# sentinel_psionic_driver.net
KiCad netlist of a schematic drawn in EAGLE
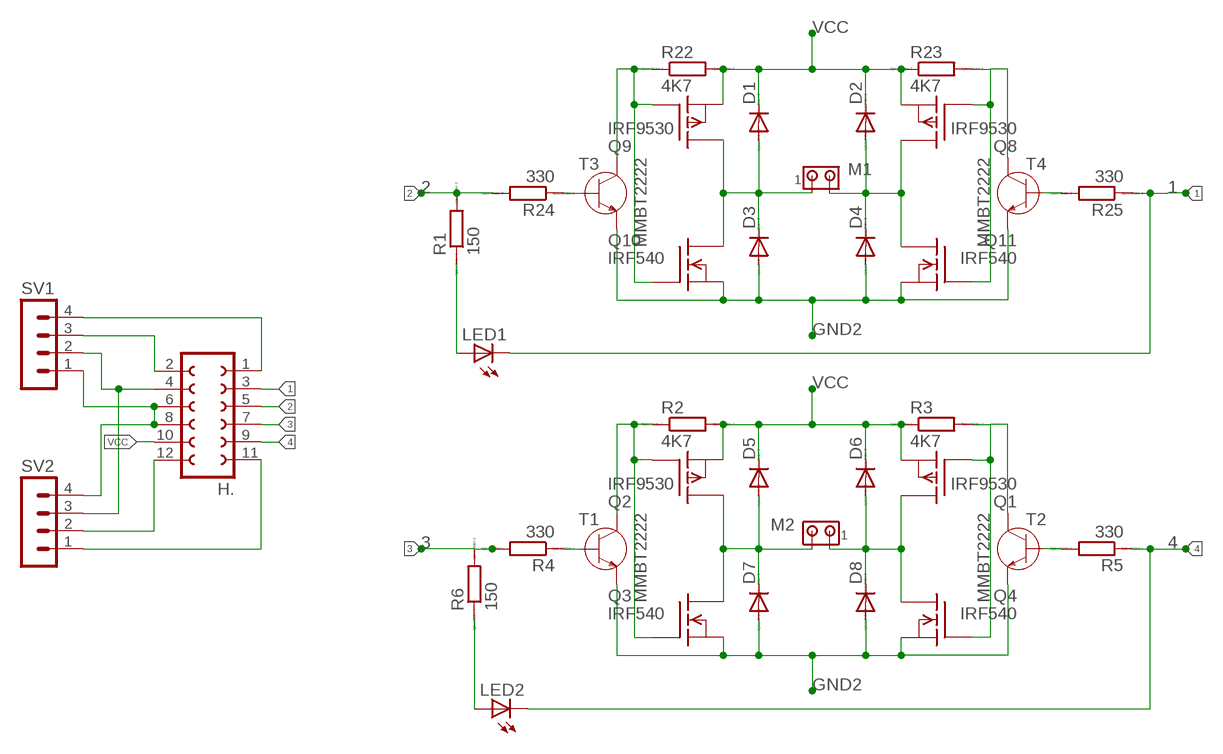
[diagram p0: schematic, sheet 1]

(export (version "E")
  (design (tool "Eeschema 10.0.6"))
  (components
    (comp (ref "D1")
      (value "DIODE-DO-214AC")
      (footprint "eagle-import:DO-214AC")
      (libsource (lib "eagle-import") (part "DIODE-DO-214AC"))
    )
    (comp (ref "D2")
      (value "DIODE-DO-214AC")
      (footprint "eagle-import:DO-214AC")
      (libsource (lib "eagle-import") (part "DIODE-DO-214AC"))
    )
    (comp (ref "D3")
      (value "DIODE-DO-214AC")
      (footprint "eagle-import:DO-214AC")
      (libsource (lib "eagle-import") (part "DIODE-DO-214AC"))
    )
    (comp (ref "D4")
      (value "DIODE-DO-214AC")
      (footprint "eagle-import:DO-214AC")
      (libsource (lib "eagle-import") (part "DIODE-DO-214AC"))
    )
    (comp (ref "D5")
      (value "DIODE-DO-214AC")
      (footprint "eagle-import:DO-214AC")
      (libsource (lib "eagle-import") (part "DIODE-DO-214AC"))
    )
    (comp (ref "D6")
      (value "DIODE-DO-214AC")
      (footprint "eagle-import:DO-214AC")
      (libsource (lib "eagle-import") (part "DIODE-DO-214AC"))
    )
    (comp (ref "D7")
      (value "DIODE-DO-214AC")
      (footprint "eagle-import:DO-214AC")
      (libsource (lib "eagle-import") (part "DIODE-DO-214AC"))
    )
    (comp (ref "D8")
      (value "DIODE-DO-214AC")
      (footprint "eagle-import:DO-214AC")
      (libsource (lib "eagle-import") (part "DIODE-DO-214AC"))
    )
    (comp (ref "H.")
      (value "FE06-2")
      (footprint "eagle-import:FE06-2")
      (libsource (lib "eagle-import") (part "FE06-2"))
    )
    (comp (ref "LED1")
      (value "LED3MM")
      (footprint "eagle-import:LED3MM")
      (libsource (lib "eagle-import") (part "LED3MM"))
    )
    (comp (ref "LED2")
      (value "LED3MM")
      (footprint "eagle-import:LED3MM")
      (libsource (lib "eagle-import") (part "LED3MM"))
    )
    (comp (ref "M1")
      (value "MTA02-100")
      (footprint "eagle-import:10X02MTA")
      (libsource (lib "eagle-import") (part "MTA02-100"))
    )
    (comp (ref "M2")
      (value "MTA02-100")
      (footprint "eagle-import:10X02MTA")
      (libsource (lib "eagle-import") (part "MTA02-100"))
    )
    (comp (ref "Q1")
      (value "IRF9530")
      (footprint "eagle-import:TO220")
      (libsource (lib "eagle-import") (part "IRF9530"))
    )
    (comp (ref "Q2")
      (value "IRF9530")
      (footprint "eagle-import:TO220")
      (libsource (lib "eagle-import") (part "IRF9530"))
    )
    (comp (ref "Q3")
      (value "IRF540")
      (footprint "eagle-import:TO220")
      (libsource (lib "eagle-import") (part "IRF540"))
    )
    (comp (ref "Q4")
      (value "IRF540")
      (footprint "eagle-import:TO220")
      (libsource (lib "eagle-import") (part "IRF540"))
    )
    (comp (ref "Q8")
      (value "IRF9530")
      (footprint "eagle-import:TO220")
      (libsource (lib "eagle-import") (part "IRF9530"))
    )
    (comp (ref "Q9")
      (value "IRF9530")
      (footprint "eagle-import:TO220")
      (libsource (lib "eagle-import") (part "IRF9530"))
    )
    (comp (ref "Q10")
      (value "IRF540")
      (footprint "eagle-import:TO220")
      (libsource (lib "eagle-import") (part "IRF540"))
    )
    (comp (ref "Q11")
      (value "IRF540")
      (footprint "eagle-import:TO220")
      (libsource (lib "eagle-import") (part "IRF540"))
    )
    (comp (ref "R1")
      (value "150")
      (footprint "eagle-import:R1206")
      (libsource (lib "eagle-import") (part "RR1206"))
    )
    (comp (ref "R2")
      (value "4K7")
      (footprint "eagle-import:R1206")
      (libsource (lib "eagle-import") (part "RR1206"))
    )
    (comp (ref "R3")
      (value "4K7")
      (footprint "eagle-import:R1206")
      (libsource (lib "eagle-import") (part "RR1206"))
    )
    (comp (ref "R4")
      (value "330")
      (footprint "eagle-import:R1206")
      (libsource (lib "eagle-import") (part "RR1206"))
    )
    (comp (ref "R5")
      (value "330")
      (footprint "eagle-import:R1206")
      (libsource (lib "eagle-import") (part "RR1206"))
    )
    (comp (ref "R6")
      (value "150")
      (footprint "eagle-import:R1206")
      (libsource (lib "eagle-import") (part "RR1206"))
    )
    (comp (ref "R22")
      (value "4K7")
      (footprint "eagle-import:R1206")
      (libsource (lib "eagle-import") (part "RR1206"))
    )
    (comp (ref "R23")
      (value "4K7")
      (footprint "eagle-import:R1206")
      (libsource (lib "eagle-import") (part "RR1206"))
    )
    (comp (ref "R24")
      (value "330")
      (footprint "eagle-import:R1206")
      (libsource (lib "eagle-import") (part "RR1206"))
    )
    (comp (ref "R25")
      (value "330")
      (footprint "eagle-import:R1206")
      (libsource (lib "eagle-import") (part "RR1206"))
    )
    (comp (ref "SV1")
      (value "MA04-1")
      (footprint "eagle-import:MA04-1")
      (libsource (lib "eagle-import") (part "MA04-1"))
    )
    (comp (ref "SV2")
      (value "MA04-1")
      (footprint "eagle-import:MA04-1")
      (libsource (lib "eagle-import") (part "MA04-1"))
    )
    (comp (ref "T1")
      (value "MMBT2222")
      (footprint "eagle-import:SOT23")
      (libsource (lib "eagle-import") (part "MMBT2222"))
    )
    (comp (ref "T2")
      (value "MMBT2222")
      (footprint "eagle-import:SOT23")
      (libsource (lib "eagle-import") (part "MMBT2222"))
    )
    (comp (ref "T3")
      (value "MMBT2222")
      (footprint "eagle-import:SOT23")
      (libsource (lib "eagle-import") (part "MMBT2222"))
    )
    (comp (ref "T4")
      (value "MMBT2222")
      (footprint "eagle-import:SOT23")
      (libsource (lib "eagle-import") (part "MMBT2222"))
    )
  )
  (nets
    (net (code "1") (name "/GND2") (class "Default")
      (node (ref "D3") (pin "A") (pinfunction "A_A") (pintype "passive"))
      (node (ref "D4") (pin "A") (pinfunction "A_A") (pintype "passive"))
      (node (ref "D7") (pin "A") (pinfunction "A_A") (pintype "passive"))
      (node (ref "D8") (pin "A") (pinfunction "A_A") (pintype "passive"))
      (node (ref "H.") (pin "6") (pinfunction "6_6") (pintype "passive"))
      (node (ref "H.") (pin "8") (pinfunction "8_8") (pintype "passive"))
      (node (ref "Q10") (pin "3") (pinfunction "S_3") (pintype "passive"))
      (node (ref "Q11") (pin "3") (pinfunction "S_3") (pintype "passive"))
      (node (ref "Q3") (pin "3") (pinfunction "S_3") (pintype "passive"))
      (node (ref "Q4") (pin "3") (pinfunction "S_3") (pintype "passive"))
      (node (ref "SV1") (pin "1") (pinfunction "1_1") (pintype "passive"))
      (node (ref "SV2") (pin "4") (pinfunction "4_4") (pintype "passive"))
      (node (ref "T1") (pin "2") (pinfunction "E_2") (pintype "passive"))
      (node (ref "T2") (pin "2") (pinfunction "E_2") (pintype "passive"))
      (node (ref "T3") (pin "2") (pinfunction "E_2") (pintype "passive"))
      (node (ref "T4") (pin "2") (pinfunction "E_2") (pintype "passive"))
    )
    (net (code "2") (name "1") (class "Default")
      (node (ref "H.") (pin "3") (pinfunction "3_3") (pintype "passive"))
      (node (ref "LED1") (pin "K") (pinfunction "C_K") (pintype "passive"))
      (node (ref "R25") (pin "1") (pinfunction "1_1") (pintype "passive"))
    )
    (net (code "3") (name "2") (class "Default")
      (node (ref "H.") (pin "5") (pinfunction "5_5") (pintype "passive"))
      (node (ref "R1") (pin "2") (pinfunction "2_2") (pintype "passive"))
      (node (ref "R24") (pin "2") (pinfunction "2_2") (pintype "passive"))
    )
    (net (code "4") (name "3") (class "Default")
      (node (ref "H.") (pin "7") (pinfunction "7_7") (pintype "passive"))
      (node (ref "R4") (pin "2") (pinfunction "2_2") (pintype "passive"))
      (node (ref "R6") (pin "2") (pinfunction "2_2") (pintype "passive"))
    )
    (net (code "5") (name "4") (class "Default")
      (node (ref "H.") (pin "9") (pinfunction "9_9") (pintype "passive"))
      (node (ref "LED2") (pin "K") (pinfunction "C_K") (pintype "passive"))
      (node (ref "R5") (pin "1") (pinfunction "1_1") (pintype "passive"))
    )
    (net (code "6") (name "Net-(H.-Pad1)") (class "Default")
      (node (ref "H.") (pin "1") (pinfunction "1_1") (pintype "passive"))
      (node (ref "SV1") (pin "4") (pinfunction "4_4") (pintype "passive"))
    )
    (net (code "7") (name "Net-(H.-Pad2)") (class "Default")
      (node (ref "H.") (pin "2") (pinfunction "2_2") (pintype "passive"))
      (node (ref "SV1") (pin "3") (pinfunction "3_3") (pintype "passive"))
    )
    (net (code "8") (name "Net-(H.-Pad4)") (class "Default")
      (node (ref "H.") (pin "4") (pinfunction "4_4") (pintype "passive"))
      (node (ref "SV1") (pin "2") (pinfunction "2_2") (pintype "passive"))
      (node (ref "SV2") (pin "3") (pinfunction "3_3") (pintype "passive"))
    )
    (net (code "9") (name "Net-(H.-Pad11)") (class "Default")
      (node (ref "H.") (pin "11") (pinfunction "11_11") (pintype "passive"))
      (node (ref "SV2") (pin "1") (pinfunction "1_1") (pintype "passive"))
    )
    (net (code "10") (name "Net-(H.-Pad12)") (class "Default")
      (node (ref "H.") (pin "12") (pinfunction "12_12") (pintype "passive"))
      (node (ref "SV2") (pin "2") (pinfunction "2_2") (pintype "passive"))
    )
    (net (code "11") (name "Net-(LED1-PadA)") (class "Default")
      (node (ref "LED1") (pin "A") (pinfunction "A_A") (pintype "passive"))
      (node (ref "R1") (pin "1") (pinfunction "1_1") (pintype "passive"))
    )
    (net (code "12") (name "Net-(LED2-PadA)") (class "Default")
      (node (ref "LED2") (pin "A") (pinfunction "A_A") (pintype "passive"))
      (node (ref "R6") (pin "1") (pinfunction "1_1") (pintype "passive"))
    )
    (net (code "13") (name "Net-(Q1-D)") (class "Default")
      (node (ref "D6") (pin "A") (pinfunction "A_A") (pintype "passive"))
      (node (ref "D8") (pin "C") (pinfunction "C_C") (pintype "passive"))
      (node (ref "M2") (pin "1") (pinfunction "1_1") (pintype "passive"))
      (node (ref "Q1") (pin "2") (pinfunction "D_2") (pintype "passive"))
      (node (ref "Q4") (pin "2") (pinfunction "D_2") (pintype "passive"))
    )
    (net (code "14") (name "Net-(Q1-G)") (class "Default")
      (node (ref "Q1") (pin "1") (pinfunction "G_1") (pintype "passive"))
      (node (ref "Q4") (pin "1") (pinfunction "G_1") (pintype "passive"))
      (node (ref "R3") (pin "2") (pinfunction "2_2") (pintype "passive"))
      (node (ref "T2") (pin "3") (pinfunction "C_3") (pintype "passive"))
    )
    (net (code "15") (name "Net-(Q2-D)") (class "Default")
      (node (ref "D5") (pin "A") (pinfunction "A_A") (pintype "passive"))
      (node (ref "D7") (pin "C") (pinfunction "C_C") (pintype "passive"))
      (node (ref "M2") (pin "2") (pinfunction "2_2") (pintype "passive"))
      (node (ref "Q2") (pin "2") (pinfunction "D_2") (pintype "passive"))
      (node (ref "Q3") (pin "2") (pinfunction "D_2") (pintype "passive"))
    )
    (net (code "16") (name "Net-(Q2-G)") (class "Default")
      (node (ref "Q2") (pin "1") (pinfunction "G_1") (pintype "passive"))
      (node (ref "Q3") (pin "1") (pinfunction "G_1") (pintype "passive"))
      (node (ref "R2") (pin "1") (pinfunction "1_1") (pintype "passive"))
      (node (ref "T1") (pin "3") (pinfunction "C_3") (pintype "passive"))
    )
    (net (code "17") (name "Net-(Q10-D)") (class "Default")
      (node (ref "D1") (pin "A") (pinfunction "A_A") (pintype "passive"))
      (node (ref "D3") (pin "C") (pinfunction "C_C") (pintype "passive"))
      (node (ref "M1") (pin "1") (pinfunction "1_1") (pintype "passive"))
      (node (ref "Q10") (pin "2") (pinfunction "D_2") (pintype "passive"))
      (node (ref "Q9") (pin "2") (pinfunction "D_2") (pintype "passive"))
    )
    (net (code "18") (name "Net-(Q10-G)") (class "Default")
      (node (ref "Q10") (pin "1") (pinfunction "G_1") (pintype "passive"))
      (node (ref "Q9") (pin "1") (pinfunction "G_1") (pintype "passive"))
      (node (ref "R22") (pin "1") (pinfunction "1_1") (pintype "passive"))
      (node (ref "T3") (pin "3") (pinfunction "C_3") (pintype "passive"))
    )
    (net (code "19") (name "Net-(Q11-D)") (class "Default")
      (node (ref "D2") (pin "A") (pinfunction "A_A") (pintype "passive"))
      (node (ref "D4") (pin "C") (pinfunction "C_C") (pintype "passive"))
      (node (ref "M1") (pin "2") (pinfunction "2_2") (pintype "passive"))
      (node (ref "Q11") (pin "2") (pinfunction "D_2") (pintype "passive"))
      (node (ref "Q8") (pin "2") (pinfunction "D_2") (pintype "passive"))
    )
    (net (code "20") (name "Net-(Q11-G)") (class "Default")
      (node (ref "Q11") (pin "1") (pinfunction "G_1") (pintype "passive"))
      (node (ref "Q8") (pin "1") (pinfunction "G_1") (pintype "passive"))
      (node (ref "R23") (pin "2") (pinfunction "2_2") (pintype "passive"))
      (node (ref "T4") (pin "3") (pinfunction "C_3") (pintype "passive"))
    )
    (net (code "21") (name "Net-(T1-B)") (class "Default")
      (node (ref "R4") (pin "1") (pinfunction "1_1") (pintype "passive"))
      (node (ref "T1") (pin "1") (pinfunction "B_1") (pintype "passive"))
    )
    (net (code "22") (name "Net-(T2-B)") (class "Default")
      (node (ref "R5") (pin "2") (pinfunction "2_2") (pintype "passive"))
      (node (ref "T2") (pin "1") (pinfunction "B_1") (pintype "passive"))
    )
    (net (code "23") (name "Net-(T3-B)") (class "Default")
      (node (ref "R24") (pin "1") (pinfunction "1_1") (pintype "passive"))
      (node (ref "T3") (pin "1") (pinfunction "B_1") (pintype "passive"))
    )
    (net (code "24") (name "Net-(T4-B)") (class "Default")
      (node (ref "R25") (pin "2") (pinfunction "2_2") (pintype "passive"))
      (node (ref "T4") (pin "1") (pinfunction "B_1") (pintype "passive"))
    )
    (net (code "25") (name "VCC") (class "Default")
      (node (ref "D1") (pin "C") (pinfunction "C_C") (pintype "passive"))
      (node (ref "D2") (pin "C") (pinfunction "C_C") (pintype "passive"))
      (node (ref "D5") (pin "C") (pinfunction "C_C") (pintype "passive"))
      (node (ref "D6") (pin "C") (pinfunction "C_C") (pintype "passive"))
      (node (ref "H.") (pin "10") (pinfunction "10_10") (pintype "passive"))
      (node (ref "Q1") (pin "3") (pinfunction "S_3") (pintype "passive"))
      (node (ref "Q2") (pin "3") (pinfunction "S_3") (pintype "passive"))
      (node (ref "Q8") (pin "3") (pinfunction "S_3") (pintype "passive"))
      (node (ref "Q9") (pin "3") (pinfunction "S_3") (pintype "passive"))
      (node (ref "R2") (pin "2") (pinfunction "2_2") (pintype "passive"))
      (node (ref "R22") (pin "2") (pinfunction "2_2") (pintype "passive"))
      (node (ref "R23") (pin "1") (pinfunction "1_1") (pintype "passive"))
      (node (ref "R3") (pin "1") (pinfunction "1_1") (pintype "passive"))
    )
  )
)
